# Sheet1.net
KiCad netlist of a schematic drawn in Altium Designer
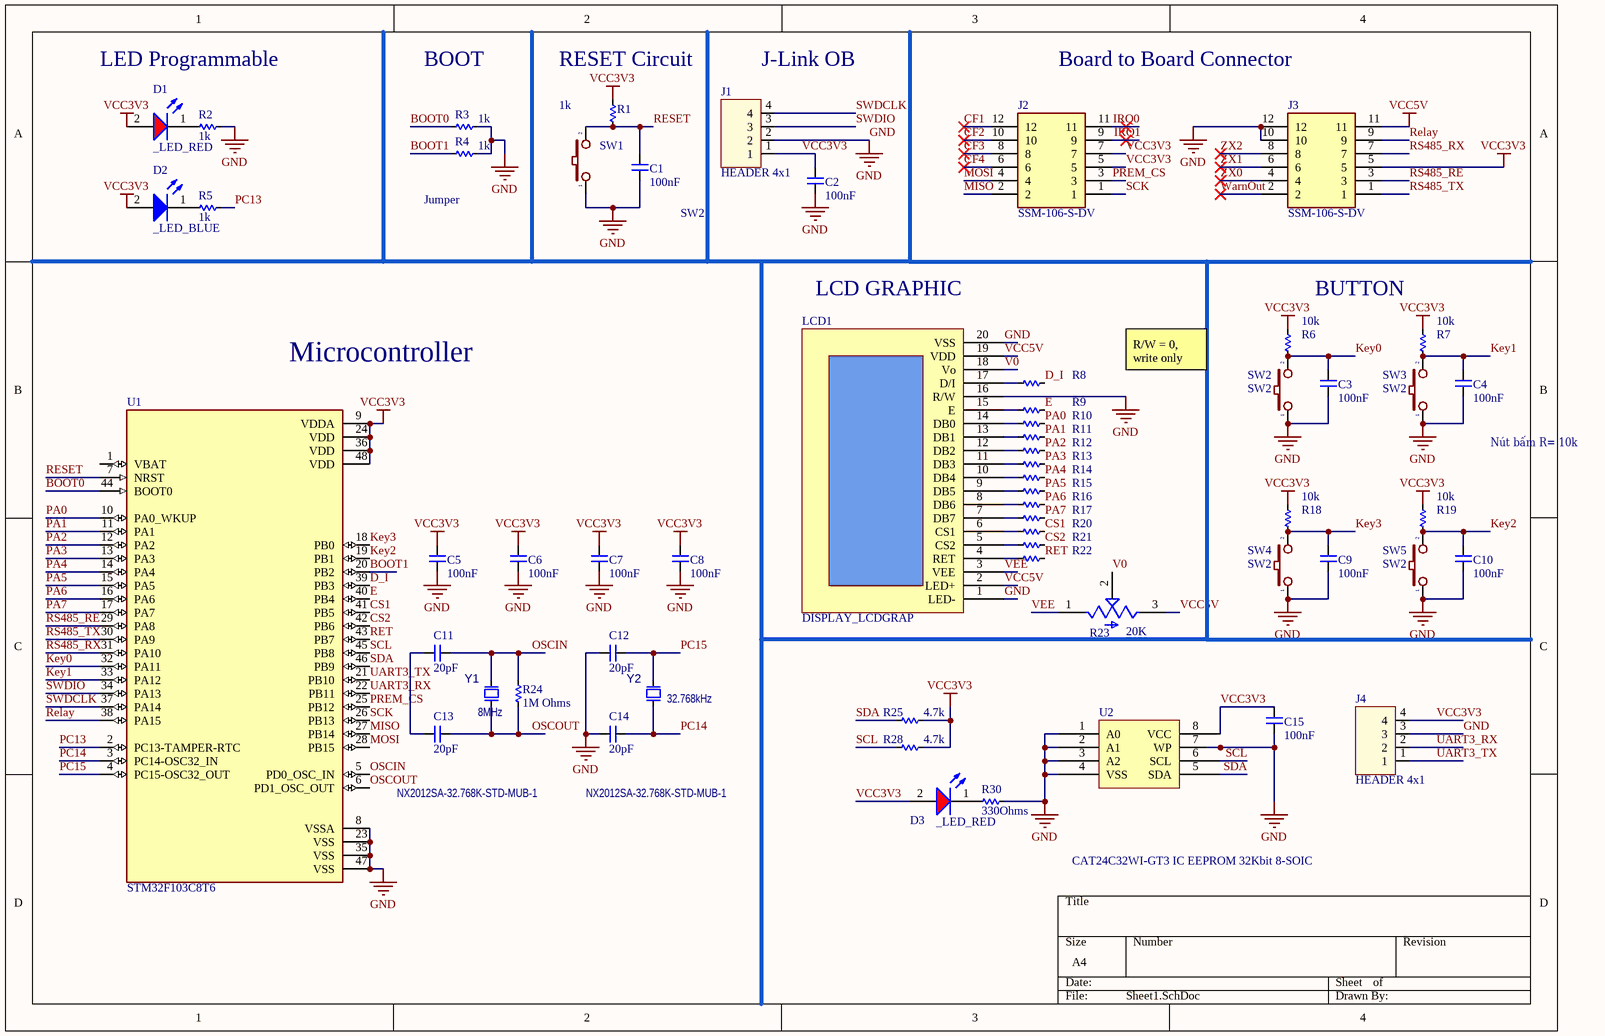
[diagram p0: Sheet1.SchDoc]

(export (version "E")
  (design (tool "Eeschema 10.0.6"))
  (components
    (comp (ref "C1")
      (value "100nF")
      (footprint "CAP_C_2012X110")
      (description "CAP")
      (libsource (lib "Logic_Control_V4") (part "_CAP_C_2"))
    )
    (comp (ref "C2")
      (value "100nF")
      (footprint "CAP_C_2012X110")
      (description "CAP")
      (libsource (lib "Logic_Control_V4") (part "_CAP_C_2"))
    )
    (comp (ref "C3")
      (value "100nF")
      (footprint "CAP_C_2012X110")
      (description "CAP")
      (libsource (lib "Logic_Control_V4") (part "_CAP_C_2"))
    )
    (comp (ref "C4")
      (value "100nF")
      (footprint "CAP_C_2012X110")
      (description "CAP")
      (libsource (lib "Logic_Control_V4") (part "_CAP_C_2"))
    )
    (comp (ref "C5")
      (value "100nF")
      (footprint "CAP_C_2012X110")
      (description "CAP")
      (libsource (lib "Logic_Control_V4") (part "_CAP_C_2"))
    )
    (comp (ref "C6")
      (value "100nF")
      (footprint "CAP_C_2012X110")
      (description "CAP")
      (libsource (lib "Logic_Control_V4") (part "_CAP_C_2"))
    )
    (comp (ref "C7")
      (value "100nF")
      (footprint "CAP_C_2012X110")
      (description "CAP")
      (libsource (lib "Logic_Control_V4") (part "_CAP_C_2"))
    )
    (comp (ref "C8")
      (value "100nF")
      (footprint "CAP_C_2012X110")
      (description "CAP")
      (libsource (lib "Logic_Control_V4") (part "_CAP_C_2"))
    )
    (comp (ref "C9")
      (value "100nF")
      (footprint "CAP_C_2012X110")
      (description "CAP")
      (libsource (lib "Logic_Control_V4") (part "_CAP_C_2"))
    )
    (comp (ref "C10")
      (value "100nF")
      (footprint "CAP_C_2012X110")
      (description "CAP")
      (libsource (lib "Logic_Control_V4") (part "_CAP_C_2"))
    )
    (comp (ref "C11")
      (value "20pF")
      (footprint "CAP_C_2012X110")
      (description "CAP")
      (libsource (lib "Logic_Control_V4") (part "_CAP_C_2"))
    )
    (comp (ref "C12")
      (value "20pF")
      (footprint "CAP_C_2012X110")
      (description "CAP")
      (libsource (lib "Logic_Control_V4") (part "_CAP_C_2"))
    )
    (comp (ref "C13")
      (value "20pF")
      (footprint "CAP_C_2012X110")
      (description "CAP")
      (libsource (lib "Logic_Control_V4") (part "_CAP_C_2"))
    )
    (comp (ref "C14")
      (value "20pF")
      (footprint "CAP_C_2012X110")
      (description "CAP")
      (libsource (lib "Logic_Control_V4") (part "_CAP_C_2"))
    )
    (comp (ref "C15")
      (value "100nF")
      (footprint "CAP_C_2012X110")
      (description "CAP")
      (libsource (lib "Logic_Control_V4") (part "_CAP_C_2"))
    )
    (comp (ref "D1")
      (value "_LED_RED")
      (footprint "LED_0603")
      (libsource (lib "Logic_Control_V4") (part "_LED_RED"))
    )
    (comp (ref "D2")
      (value "_LED_BLUE")
      (footprint "LED_0603")
      (libsource (lib "Logic_Control_V4") (part "_LED_BLUE"))
    )
    (comp (ref "D3")
      (value "_LED_RED")
      (footprint "LED_0603")
      (libsource (lib "Logic_Control_V4") (part "_LED_RED"))
    )
    (comp (ref "J1")
      (value "HEADER 4x1")
      (footprint "Header_254P_4x1")
      (libsource (lib "Logic_Control_V4") (part "Header 4x1"))
    )
    (comp (ref "J2")
      (value "SSM-106-S-DV")
      (footprint "SSM-105-XXX-DV-BE")
      (description "Connector")
      (fields
        (field (name "MANUFACTURER_PART_NUMBER") "SSM-105-S-DV")
        (field (name "MOUSER PART NUMBER") "200-SSM105SDV")
      )
      (libsource (lib "LogicControl_V2") (part "SSM-106-S-DV"))
    )
    (comp (ref "J3")
      (value "SSM-106-S-DV")
      (footprint "SSM-105-XXX-DV-BE")
      (description "Connector")
      (fields
        (field (name "MANUFACTURER_PART_NUMBER") "SSM-105-S-DV")
        (field (name "MOUSER PART NUMBER") "200-SSM105SDV")
      )
      (libsource (lib "LogicControl_V2") (part "SSM-106-S-DV"))
    )
    (comp (ref "J4")
      (value "HEADER 4x1")
      (footprint "Header_254P_4x1")
      (libsource (lib "Logic_Control_V4") (part "Header 4x1"))
    )
    (comp (ref "LCD1")
      (value "DISPLAY_LCDGRAP")
      (footprint "LCD_GRAP_20PIN")
      (description "Display 128x64pixel")
      (fields
        (field (name "MANUFACTURER") "Newhaven Display")
        (field (name "MANUFACTURER PART NUMBER") "NHD-12864AZ-NSW-BBW-TR")
      )
      (libsource (lib "Logic_Control_V4") (part "DISPLAY_LCDGRAP"))
    )
    (comp (ref "R1")
      (value "1k")
      (footprint "RES_C_2012X65")
      (description "RES")
      (libsource (lib "Logic_Control_V4") (part "_RES_B_2"))
    )
    (comp (ref "R2")
      (value "1k")
      (footprint "RES_C_2012X65")
      (description "RES")
      (libsource (lib "Logic_Control_V4") (part "_RES_B_2"))
    )
    (comp (ref "R3")
      (value "1k")
      (footprint "RES_C_2012X65")
      (description "RES")
      (libsource (lib "Logic_Control_V4") (part "_RES_B_2"))
    )
    (comp (ref "R4")
      (value "1k")
      (footprint "RES_C_2012X65")
      (description "RES")
      (libsource (lib "Logic_Control_V4") (part "_RES_B_2"))
    )
    (comp (ref "R5")
      (value "1k")
      (footprint "RES_C_2012X65")
      (description "RES")
      (libsource (lib "Logic_Control_V4") (part "_RES_B_2"))
    )
    (comp (ref "R6")
      (value "10k")
      (footprint "RES_C_2012X65")
      (description "RES")
      (libsource (lib "Logic_Control_V4") (part "_RES_B_2"))
    )
    (comp (ref "R7")
      (value "10k")
      (footprint "RES_C_2012X65")
      (description "RES")
      (libsource (lib "Logic_Control_V4") (part "_RES_B_2"))
    )
    (comp (ref "R8")
      (value "1k")
      (footprint "RES_C_2012X65")
      (description "RES")
      (libsource (lib "Logic_Control_V4") (part "_RES_B_2"))
    )
    (comp (ref "R9")
      (value "1k")
      (footprint "RES_C_2012X65")
      (description "RES")
      (libsource (lib "Logic_Control_V4") (part "_RES_B_2"))
    )
    (comp (ref "R10")
      (value "1k")
      (footprint "RES_C_2012X65")
      (description "RES")
      (libsource (lib "Logic_Control_V4") (part "_RES_B_2"))
    )
    (comp (ref "R11")
      (value "1k")
      (footprint "RES_C_2012X65")
      (description "RES")
      (libsource (lib "Logic_Control_V4") (part "_RES_B_2"))
    )
    (comp (ref "R12")
      (value "1k")
      (footprint "RES_C_2012X65")
      (description "RES")
      (libsource (lib "Logic_Control_V4") (part "_RES_B_2"))
    )
    (comp (ref "R13")
      (value "1k")
      (footprint "RES_C_2012X65")
      (description "RES")
      (libsource (lib "Logic_Control_V4") (part "_RES_B_2"))
    )
    (comp (ref "R14")
      (value "1k")
      (footprint "RES_C_2012X65")
      (description "RES")
      (libsource (lib "Logic_Control_V4") (part "_RES_B_2"))
    )
    (comp (ref "R15")
      (value "1k")
      (footprint "RES_C_2012X65")
      (description "RES")
      (libsource (lib "Logic_Control_V4") (part "_RES_B_2"))
    )
    (comp (ref "R16")
      (value "1k")
      (footprint "RES_C_2012X65")
      (description "RES")
      (libsource (lib "Logic_Control_V4") (part "_RES_B_2"))
    )
    (comp (ref "R17")
      (value "1k")
      (footprint "RES_C_2012X65")
      (description "RES")
      (libsource (lib "Logic_Control_V4") (part "_RES_B_2"))
    )
    (comp (ref "R18")
      (value "10k")
      (footprint "RES_C_2012X65")
      (description "RES")
      (libsource (lib "Logic_Control_V4") (part "_RES_B_2"))
    )
    (comp (ref "R19")
      (value "10k")
      (footprint "RES_C_2012X65")
      (description "RES")
      (libsource (lib "Logic_Control_V4") (part "_RES_B_2"))
    )
    (comp (ref "R20")
      (value "1k")
      (footprint "RES_C_2012X65")
      (description "RES")
      (libsource (lib "Logic_Control_V4") (part "_RES_B_2"))
    )
    (comp (ref "R21")
      (value "1k")
      (footprint "RES_C_2012X65")
      (description "RES")
      (libsource (lib "Logic_Control_V4") (part "_RES_B_2"))
    )
    (comp (ref "R22")
      (value "1k")
      (footprint "RES_C_2012X65")
      (description "RES")
      (libsource (lib "Logic_Control_V4") (part "_RES_B_2"))
    )
    (comp (ref "R23")
      (value "20K")
      (footprint "TRIM_TC33X-2-103E")
      (description "10 kOhms 0.1W, 1/10W J Lead Surface Mount Trimmer Potentiometer Cermet 1 Turn Top Adjustment")
      (fields (field (name "MP") "TC33X-2-103E") (field (name "MF") "Bourns"))
      (libsource (lib "Logic_Control_V4") (part "TC33X-2-103E"))
    )
    (comp (ref "R24")
      (value "1M Ohms")
      (footprint "RES_C_2012X65")
      (description "RES")
      (libsource (lib "Logic_Control_V4") (part "_RES_B_2"))
    )
    (comp (ref "R25")
      (value "4.7k")
      (footprint "RES_C_1608X60")
      (description "RES")
      (libsource (lib "Logic_Control_V4") (part "_RES_B_2_1"))
    )
    (comp (ref "R28")
      (value "4.7k")
      (footprint "RES_C_1608X60")
      (description "RES")
      (libsource (lib "Logic_Control_V4") (part "_RES_B_2_1"))
    )
    (comp (ref "R30")
      (value "330Ohms")
      (footprint "RES_C_1608X60")
      (description "RES")
      (libsource (lib "Logic_Control_V4") (part "_RES_B_2_1"))
    )
    (comp (ref "SW1")
      (value "SW2")
      (footprint "SW2-SMD")
      (description "Switch button 2 pin")
      (libsource (lib "Logic_Control_V4") (part "SW2"))
    )
    (comp (ref "SW2")
      (value "SW2")
      (footprint "SW2-SMD")
      (description "Switch button 2 pin")
      (libsource (lib "Logic_Control_V4") (part "SW2"))
    )
    (comp (ref "SW3")
      (value "SW2")
      (footprint "SW2-SMD")
      (description "Switch button 2 pin")
      (libsource (lib "Logic_Control_V4") (part "SW2"))
    )
    (comp (ref "SW4")
      (value "SW2")
      (footprint "SW2-SMD")
      (description "Switch button 2 pin")
      (libsource (lib "Logic_Control_V4") (part "SW2"))
    )
    (comp (ref "SW5")
      (value "SW2")
      (footprint "SW2-SMD")
      (description "Switch button 2 pin")
      (libsource (lib "Logic_Control_V4") (part "SW2"))
    )
    (comp (ref "U1")
      (value "STM32F103C8T6")
      (footprint "QFP50P900X900X160-48N")
      (description "ARM® Cortex®-M3 STM32F1 Microcontroller IC 32-Bit 72MHz 64KB (64K x 8) FLASH 48-LQFP (7x7)")
      (fields (field (name "MF") "STMicroelectronics"))
      (libsource (lib "Logic_Control_V4") (part "STM32F103C8T6"))
    )
    (comp (ref "U2")
      (value "CAT24C32WI-GT3 IC EEPROM 32Kbit 8-SOIC")
      (footprint "SOP8")
      (libsource (lib "Logic_Control_V4") (part "CAT24C32WI-GT3 IC EEPROM 32Kbit 8-SOIC"))
    )
    (comp (ref "Y1")
      (value "8MHz")
      (footprint "CRYSTAL_NX2012SA")
      (description "Crystal")
      (fields
        (field (name "TOLERANCE") "±20ppm")
        (field (name "MANUFACTURER PART NUMBER 1") "NX2012SA-32.768K-STD-MUB-1")
        (field (name "Comment") "Crystal 2 Pins")
        (field (name "OWNER") "Jamus Griego")
      )
      (libsource (lib "Logic_Control_V4") (part "OSC_32.768kHz"))
    )
    (comp (ref "Y2")
      (value "32.768kHz")
      (footprint "CRYSTAL_NX2012SA")
      (description "Crystal")
      (fields
        (field (name "TOLERANCE") "±20ppm")
        (field (name "MANUFACTURER PART NUMBER 1") "NX2012SA-32.768K-STD-MUB-1")
        (field (name "Comment") "Crystal 2 Pins")
        (field (name "OWNER") "Jamus Griego")
      )
      (libsource (lib "Logic_Control_V4") (part "OSC_32.768kHz"))
    )
  )
  (nets
    (net (code "1") (name "/BOOT0") (class "Default")
      (node (ref "R3") (pin "1") (pinfunction "1_1") (pintype "passive"))
      (node (ref "U1") (pin "44") (pinfunction "BOOT0_44") (pintype "input"))
    )
    (net (code "2") (name "/BOOT1") (class "Default")
      (node (ref "R4") (pin "1") (pinfunction "1_1") (pintype "passive"))
      (node (ref "U1") (pin "20") (pinfunction "PB2_20") (pintype "bidirectional"))
    )
    (net (code "3") (name "/CF1") (class "Default")
      (node (ref "J2") (pin "12") (pinfunction "12_12") (pintype "passive+no_connect"))
    )
    (net (code "4") (name "/CF2") (class "Default")
      (node (ref "J2") (pin "10") (pinfunction "10_10") (pintype "passive+no_connect"))
    )
    (net (code "5") (name "/CF3") (class "Default")
      (node (ref "J2") (pin "8") (pinfunction "8_8") (pintype "passive+no_connect"))
    )
    (net (code "6") (name "/CF4") (class "Default")
      (node (ref "J2") (pin "6") (pinfunction "6_6") (pintype "passive+no_connect"))
    )
    (net (code "7") (name "/CS1") (class "Default")
      (node (ref "R20") (pin "2") (pinfunction "2_2") (pintype "passive"))
      (node (ref "U1") (pin "41") (pinfunction "PB5_41") (pintype "bidirectional"))
    )
    (net (code "8") (name "/CS2") (class "Default")
      (node (ref "R21") (pin "2") (pinfunction "2_2") (pintype "passive"))
      (node (ref "U1") (pin "42") (pinfunction "PB6_42") (pintype "bidirectional"))
    )
    (net (code "9") (name "/D_I") (class "Default")
      (node (ref "R8") (pin "2") (pinfunction "2_2") (pintype "passive"))
      (node (ref "U1") (pin "39") (pinfunction "PB3_39") (pintype "bidirectional"))
    )
    (net (code "10") (name "/E") (class "Default")
      (node (ref "R9") (pin "2") (pinfunction "2_2") (pintype "passive"))
      (node (ref "U1") (pin "40") (pinfunction "PB4_40") (pintype "bidirectional"))
    )
    (net (code "11") (name "/IRQ0") (class "Default")
      (node (ref "J2") (pin "11") (pinfunction "11_11") (pintype "passive"))
    )
    (net (code "12") (name "/IRQ1") (class "Default")
      (node (ref "J2") (pin "9") (pinfunction "9_9") (pintype "passive"))
    )
    (net (code "13") (name "/Key0") (class "Default")
      (node (ref "C3") (pin "2") (pinfunction "2_2") (pintype "passive"))
      (node (ref "R6") (pin "1") (pinfunction "1_1") (pintype "passive"))
      (node (ref "SW2") (pin "2") (pinfunction "2_2") (pintype "passive"))
      (node (ref "U1") (pin "32") (pinfunction "PA11_32") (pintype "bidirectional"))
    )
    (net (code "14") (name "/Key1") (class "Default")
      (node (ref "C4") (pin "2") (pinfunction "2_2") (pintype "passive"))
      (node (ref "R7") (pin "1") (pinfunction "1_1") (pintype "passive"))
      (node (ref "SW3") (pin "2") (pinfunction "2_2") (pintype "passive"))
      (node (ref "U1") (pin "33") (pinfunction "PA12_33") (pintype "bidirectional"))
    )
    (net (code "15") (name "/Key2") (class "Default")
      (node (ref "C10") (pin "2") (pinfunction "2_2") (pintype "passive"))
      (node (ref "R19") (pin "1") (pinfunction "1_1") (pintype "passive"))
      (node (ref "SW5") (pin "2") (pinfunction "2_2") (pintype "passive"))
      (node (ref "U1") (pin "19") (pinfunction "PB1_19") (pintype "bidirectional"))
    )
    (net (code "16") (name "/Key3") (class "Default")
      (node (ref "C9") (pin "2") (pinfunction "2_2") (pintype "passive"))
      (node (ref "R18") (pin "1") (pinfunction "1_1") (pintype "passive"))
      (node (ref "SW4") (pin "2") (pinfunction "2_2") (pintype "passive"))
      (node (ref "U1") (pin "18") (pinfunction "PB0_18") (pintype "bidirectional"))
    )
    (net (code "17") (name "/MISO") (class "Default")
      (node (ref "J2") (pin "2") (pinfunction "2_2") (pintype "passive"))
      (node (ref "U1") (pin "27") (pinfunction "PB14_27") (pintype "bidirectional"))
    )
    (net (code "18") (name "/MOSI") (class "Default")
      (node (ref "J2") (pin "4") (pinfunction "4_4") (pintype "passive"))
      (node (ref "U1") (pin "28") (pinfunction "PB15_28") (pintype "bidirectional"))
    )
    (net (code "19") (name "/OSCIN") (class "Default")
      (node (ref "C11") (pin "2") (pinfunction "2_2") (pintype "passive"))
      (node (ref "R24") (pin "2") (pinfunction "2_2") (pintype "passive"))
      (node (ref "U1") (pin "5") (pinfunction "PD0_OSC_IN_5") (pintype "bidirectional"))
      (node (ref "Y1") (pin "2") (pinfunction "Osc2_2") (pintype "passive"))
    )
    (net (code "20") (name "/OSCOUT") (class "Default")
      (node (ref "C13") (pin "2") (pinfunction "2_2") (pintype "passive"))
      (node (ref "R24") (pin "1") (pinfunction "1_1") (pintype "passive"))
      (node (ref "U1") (pin "6") (pinfunction "PD1_OSC_OUT_6") (pintype "bidirectional"))
      (node (ref "Y1") (pin "1") (pinfunction "Osc1_1") (pintype "passive"))
    )
    (net (code "21") (name "/PA0") (class "Default")
      (node (ref "R10") (pin "2") (pinfunction "2_2") (pintype "passive"))
      (node (ref "U1") (pin "10") (pinfunction "PA0_WKUP_10") (pintype "bidirectional"))
    )
    (net (code "22") (name "/PA1") (class "Default")
      (node (ref "R11") (pin "2") (pinfunction "2_2") (pintype "passive"))
      (node (ref "U1") (pin "11") (pinfunction "PA1_11") (pintype "bidirectional"))
    )
    (net (code "23") (name "/PA2") (class "Default")
      (node (ref "R12") (pin "2") (pinfunction "2_2") (pintype "passive"))
      (node (ref "U1") (pin "12") (pinfunction "PA2_12") (pintype "bidirectional"))
    )
    (net (code "24") (name "/PA3") (class "Default")
      (node (ref "R13") (pin "2") (pinfunction "2_2") (pintype "passive"))
      (node (ref "U1") (pin "13") (pinfunction "PA3_13") (pintype "bidirectional"))
    )
    (net (code "25") (name "/PA4") (class "Default")
      (node (ref "R14") (pin "2") (pinfunction "2_2") (pintype "passive"))
      (node (ref "U1") (pin "14") (pinfunction "PA4_14") (pintype "bidirectional"))
    )
    (net (code "26") (name "/PA5") (class "Default")
      (node (ref "R15") (pin "2") (pinfunction "2_2") (pintype "passive"))
      (node (ref "U1") (pin "15") (pinfunction "PA5_15") (pintype "bidirectional"))
    )
    (net (code "27") (name "/PA6") (class "Default")
      (node (ref "R16") (pin "2") (pinfunction "2_2") (pintype "passive"))
      (node (ref "U1") (pin "16") (pinfunction "PA6_16") (pintype "bidirectional"))
    )
    (net (code "28") (name "/PA7") (class "Default")
      (node (ref "R17") (pin "2") (pinfunction "2_2") (pintype "passive"))
      (node (ref "U1") (pin "17") (pinfunction "PA7_17") (pintype "bidirectional"))
    )
    (net (code "29") (name "/PC13") (class "Default")
      (node (ref "R5") (pin "2") (pinfunction "2_2") (pintype "passive"))
      (node (ref "U1") (pin "2") (pinfunction "PC13-TAMPER-RTC_2") (pintype "bidirectional"))
    )
    (net (code "30") (name "/PC14") (class "Default")
      (node (ref "C14") (pin "2") (pinfunction "2_2") (pintype "passive"))
      (node (ref "U1") (pin "3") (pinfunction "PC14-OSC32_IN_3") (pintype "bidirectional"))
      (node (ref "Y2") (pin "1") (pinfunction "Osc1_1") (pintype "passive"))
    )
    (net (code "31") (name "/PC15") (class "Default")
      (node (ref "C12") (pin "2") (pinfunction "2_2") (pintype "passive"))
      (node (ref "U1") (pin "4") (pinfunction "PC15-OSC32_OUT_4") (pintype "bidirectional"))
      (node (ref "Y2") (pin "2") (pinfunction "Osc2_2") (pintype "passive"))
    )
    (net (code "32") (name "/PREM_CS") (class "Default")
      (node (ref "J2") (pin "3") (pinfunction "3_3") (pintype "passive"))
      (node (ref "U1") (pin "25") (pinfunction "PB12_25") (pintype "bidirectional"))
    )
    (net (code "33") (name "/RESET") (class "Default")
      (node (ref "C1") (pin "2") (pinfunction "2_2") (pintype "passive"))
      (node (ref "R1") (pin "1") (pinfunction "1_1") (pintype "passive"))
      (node (ref "SW1") (pin "2") (pinfunction "2_2") (pintype "passive"))
      (node (ref "U1") (pin "7") (pinfunction "NRST_7") (pintype "input"))
    )
    (net (code "34") (name "/RET") (class "Default")
      (node (ref "R22") (pin "2") (pinfunction "2_2") (pintype "passive"))
      (node (ref "U1") (pin "43") (pinfunction "PB7_43") (pintype "bidirectional"))
    )
    (net (code "35") (name "/RS485_RE") (class "Default")
      (node (ref "J3") (pin "3") (pinfunction "3_3") (pintype "passive"))
      (node (ref "U1") (pin "29") (pinfunction "PA8_29") (pintype "bidirectional"))
    )
    (net (code "36") (name "/RS485_RX") (class "Default")
      (node (ref "J3") (pin "7") (pinfunction "7_7") (pintype "passive"))
      (node (ref "U1") (pin "31") (pinfunction "PA10_31") (pintype "bidirectional"))
    )
    (net (code "37") (name "/RS485_TX") (class "Default")
      (node (ref "J3") (pin "1") (pinfunction "1_1") (pintype "passive"))
      (node (ref "U1") (pin "30") (pinfunction "PA9_30") (pintype "bidirectional"))
    )
    (net (code "38") (name "/Relay") (class "Default")
      (node (ref "J3") (pin "9") (pinfunction "9_9") (pintype "passive"))
      (node (ref "U1") (pin "38") (pinfunction "PA15_38") (pintype "bidirectional"))
    )
    (net (code "39") (name "/SCK") (class "Default")
      (node (ref "J2") (pin "1") (pinfunction "1_1") (pintype "passive"))
      (node (ref "U1") (pin "26") (pinfunction "PB13_26") (pintype "bidirectional"))
    )
    (net (code "40") (name "/SCL") (class "Default")
      (node (ref "R28") (pin "1") (pinfunction "1_1") (pintype "passive"))
      (node (ref "U1") (pin "45") (pinfunction "PB8_45") (pintype "bidirectional"))
      (node (ref "U2") (pin "6") (pinfunction "SCL_6") (pintype "passive"))
    )
    (net (code "41") (name "/SDA") (class "Default")
      (node (ref "R25") (pin "1") (pinfunction "1_1") (pintype "passive"))
      (node (ref "U1") (pin "46") (pinfunction "PB9_46") (pintype "bidirectional"))
      (node (ref "U2") (pin "5") (pinfunction "SDA_5") (pintype "passive"))
    )
    (net (code "42") (name "/SWDCLK") (class "Default")
      (node (ref "J1") (pin "4") (pinfunction "4_4") (pintype "passive"))
      (node (ref "U1") (pin "37") (pinfunction "PA14_37") (pintype "bidirectional"))
    )
    (net (code "43") (name "/SWDIO") (class "Default")
      (node (ref "J1") (pin "3") (pinfunction "3_3") (pintype "passive"))
      (node (ref "U1") (pin "34") (pinfunction "PA13_34") (pintype "bidirectional"))
    )
    (net (code "44") (name "/UART3_RX") (class "Default")
      (node (ref "J4") (pin "2") (pinfunction "2_2") (pintype "passive"))
      (node (ref "U1") (pin "22") (pinfunction "PB11_22") (pintype "bidirectional"))
    )
    (net (code "45") (name "/UART3_TX") (class "Default")
      (node (ref "J4") (pin "1") (pinfunction "1_1") (pintype "passive"))
      (node (ref "U1") (pin "21") (pinfunction "PB10_21") (pintype "bidirectional"))
    )
    (net (code "46") (name "/V0") (class "Default")
      (node (ref "LCD1") (pin "18") (pinfunction "Vo_18") (pintype "power_in"))
      (node (ref "R23") (pin "2") (pinfunction "W_2") (pintype "passive"))
    )
    (net (code "47") (name "/VEE") (class "Default")
      (node (ref "LCD1") (pin "3") (pinfunction "VEE_3") (pintype "power_in"))
      (node (ref "R23") (pin "1") (pinfunction "CCW_1") (pintype "passive"))
    )
    (net (code "48") (name "/WarnOut") (class "Default")
      (node (ref "J3") (pin "2") (pinfunction "2_2") (pintype "passive+no_connect"))
    )
    (net (code "49") (name "/ZX0") (class "Default")
      (node (ref "J3") (pin "4") (pinfunction "4_4") (pintype "passive+no_connect"))
    )
    (net (code "50") (name "/ZX1") (class "Default")
      (node (ref "J3") (pin "6") (pinfunction "6_6") (pintype "passive+no_connect"))
    )
    (net (code "51") (name "/ZX2") (class "Default")
      (node (ref "J3") (pin "8") (pinfunction "8_8") (pintype "passive+no_connect"))
    )
    (net (code "52") (name "GND") (class "Default")
      (node (ref "C1") (pin "1") (pinfunction "1_1") (pintype "passive"))
      (node (ref "C10") (pin "1") (pinfunction "1_1") (pintype "passive"))
      (node (ref "C12") (pin "1") (pinfunction "1_1") (pintype "passive"))
      (node (ref "C14") (pin "1") (pinfunction "1_1") (pintype "passive"))
      (node (ref "C15") (pin "1") (pinfunction "1_1") (pintype "passive"))
      (node (ref "C2") (pin "1") (pinfunction "1_1") (pintype "passive"))
      (node (ref "C3") (pin "1") (pinfunction "1_1") (pintype "passive"))
      (node (ref "C4") (pin "1") (pinfunction "1_1") (pintype "passive"))
      (node (ref "C5") (pin "1") (pinfunction "1_1") (pintype "passive"))
      (node (ref "C6") (pin "1") (pinfunction "1_1") (pintype "passive"))
      (node (ref "C7") (pin "1") (pinfunction "1_1") (pintype "passive"))
      (node (ref "C8") (pin "1") (pinfunction "1_1") (pintype "passive"))
      (node (ref "C9") (pin "1") (pinfunction "1_1") (pintype "passive"))
      (node (ref "J1") (pin "2") (pinfunction "2_2") (pintype "passive"))
      (node (ref "J3") (pin "10") (pinfunction "10_10") (pintype "passive"))
      (node (ref "J3") (pin "12") (pinfunction "12_12") (pintype "passive"))
      (node (ref "J4") (pin "3") (pinfunction "3_3") (pintype "passive"))
      (node (ref "LCD1") (pin "1") (pinfunction "LED-_1") (pintype "power_in"))
      (node (ref "LCD1") (pin "16") (pinfunction "R/W_16") (pintype "passive"))
      (node (ref "LCD1") (pin "20") (pinfunction "VSS_20") (pintype "power_in"))
      (node (ref "R2") (pin "2") (pinfunction "2_2") (pintype "passive"))
      (node (ref "R3") (pin "2") (pinfunction "2_2") (pintype "passive"))
      (node (ref "R30") (pin "2") (pinfunction "2_2") (pintype "passive"))
      (node (ref "R4") (pin "2") (pinfunction "2_2") (pintype "passive"))
      (node (ref "SW1") (pin "1") (pinfunction "1_1") (pintype "passive"))
      (node (ref "SW2") (pin "1") (pinfunction "1_1") (pintype "passive"))
      (node (ref "SW3") (pin "1") (pinfunction "1_1") (pintype "passive"))
      (node (ref "SW4") (pin "1") (pinfunction "1_1") (pintype "passive"))
      (node (ref "SW5") (pin "1") (pinfunction "1_1") (pintype "passive"))
      (node (ref "U1") (pin "23") (pinfunction "VSS_23") (pintype "power_in"))
      (node (ref "U1") (pin "35") (pinfunction "VSS_35") (pintype "power_in"))
      (node (ref "U1") (pin "47") (pinfunction "VSS_47") (pintype "power_in"))
      (node (ref "U1") (pin "8") (pinfunction "VSSA_8") (pintype "power_in"))
      (node (ref "U2") (pin "1") (pinfunction "A0_1") (pintype "passive"))
      (node (ref "U2") (pin "2") (pinfunction "A1_2") (pintype "passive"))
      (node (ref "U2") (pin "3") (pinfunction "A2_3") (pintype "passive"))
      (node (ref "U2") (pin "4") (pinfunction "VSS_4") (pintype "passive"))
      (node (ref "U2") (pin "7") (pinfunction "WP_7") (pintype "passive"))
    )
    (net (code "53") (name "Net-(C11-Pad1)") (class "Default")
      (node (ref "C11") (pin "1") (pinfunction "1_1") (pintype "passive"))
      (node (ref "C13") (pin "1") (pinfunction "1_1") (pintype "passive"))
    )
    (net (code "54") (name "Net-(D1-K)") (class "Default")
      (node (ref "D1") (pin "1") (pinfunction "K_1") (pintype "passive"))
      (node (ref "R2") (pin "1") (pinfunction "1_1") (pintype "passive"))
    )
    (net (code "55") (name "Net-(D2-K)") (class "Default")
      (node (ref "D2") (pin "1") (pinfunction "K_1") (pintype "passive"))
      (node (ref "R5") (pin "1") (pinfunction "1_1") (pintype "passive"))
    )
    (net (code "56") (name "Net-(D3-K)") (class "Default")
      (node (ref "D3") (pin "1") (pinfunction "K_1") (pintype "passive"))
      (node (ref "R30") (pin "1") (pinfunction "1_1") (pintype "passive"))
    )
    (net (code "57") (name "Net-(LCD1-CS1)") (class "Default")
      (node (ref "LCD1") (pin "6") (pinfunction "CS1_6") (pintype "passive"))
      (node (ref "R20") (pin "1") (pinfunction "1_1") (pintype "passive"))
    )
    (net (code "58") (name "Net-(LCD1-CS2)") (class "Default")
      (node (ref "LCD1") (pin "5") (pinfunction "CS2_5") (pintype "passive"))
      (node (ref "R21") (pin "1") (pinfunction "1_1") (pintype "passive"))
    )
    (net (code "59") (name "Net-(LCD1-DB0)") (class "Default")
      (node (ref "LCD1") (pin "14") (pinfunction "DB0_14") (pintype "passive"))
      (node (ref "R10") (pin "1") (pinfunction "1_1") (pintype "passive"))
    )
    (net (code "60") (name "Net-(LCD1-DB1)") (class "Default")
      (node (ref "LCD1") (pin "13") (pinfunction "DB1_13") (pintype "passive"))
      (node (ref "R11") (pin "1") (pinfunction "1_1") (pintype "passive"))
    )
    (net (code "61") (name "Net-(LCD1-DB2)") (class "Default")
      (node (ref "LCD1") (pin "12") (pinfunction "DB2_12") (pintype "passive"))
      (node (ref "R12") (pin "1") (pinfunction "1_1") (pintype "passive"))
    )
    (net (code "62") (name "Net-(LCD1-DB3)") (class "Default")
      (node (ref "LCD1") (pin "11") (pinfunction "DB3_11") (pintype "passive"))
      (node (ref "R13") (pin "1") (pinfunction "1_1") (pintype "passive"))
    )
    (net (code "63") (name "Net-(LCD1-DB4)") (class "Default")
      (node (ref "LCD1") (pin "10") (pinfunction "DB4_10") (pintype "passive"))
      (node (ref "R14") (pin "1") (pinfunction "1_1") (pintype "passive"))
    )
    (net (code "64") (name "Net-(LCD1-DB5)") (class "Default")
      (node (ref "LCD1") (pin "9") (pinfunction "DB5_9") (pintype "passive"))
      (node (ref "R15") (pin "1") (pinfunction "1_1") (pintype "passive"))
    )
    (net (code "65") (name "Net-(LCD1-DB6)") (class "Default")
      (node (ref "LCD1") (pin "8") (pinfunction "DB6_8") (pintype "passive"))
      (node (ref "R16") (pin "1") (pinfunction "1_1") (pintype "passive"))
    )
    (net (code "66") (name "Net-(LCD1-DB7)") (class "Default")
      (node (ref "LCD1") (pin "7") (pinfunction "DB7_7") (pintype "passive"))
      (node (ref "R17") (pin "1") (pinfunction "1_1") (pintype "passive"))
    )
    (net (code "67") (name "Net-(LCD1-D{slash}I)") (class "Default")
      (node (ref "LCD1") (pin "17") (pinfunction "D/I_17") (pintype "passive"))
      (node (ref "R8") (pin "1") (pinfunction "1_1") (pintype "passive"))
    )
    (net (code "68") (name "Net-(LCD1-E)") (class "Default")
      (node (ref "LCD1") (pin "15") (pinfunction "E_15") (pintype "passive"))
      (node (ref "R9") (pin "1") (pinfunction "1_1") (pintype "passive"))
    )
    (net (code "69") (name "Net-(LCD1-RET)") (class "Default")
      (node (ref "LCD1") (pin "4") (pinfunction "RET_4") (pintype "passive"))
      (node (ref "R22") (pin "1") (pinfunction "1_1") (pintype "passive"))
    )
    (net (code "70") (name "VCC3V3") (class "Default")
      (node (ref "C15") (pin "2") (pinfunction "2_2") (pintype "passive"))
      (node (ref "C2") (pin "2") (pinfunction "2_2") (pintype "passive"))
      (node (ref "C5") (pin "2") (pinfunction "2_2") (pintype "passive"))
      (node (ref "C6") (pin "2") (pinfunction "2_2") (pintype "passive"))
      (node (ref "C7") (pin "2") (pinfunction "2_2") (pintype "passive"))
      (node (ref "C8") (pin "2") (pinfunction "2_2") (pintype "passive"))
      (node (ref "D1") (pin "2") (pinfunction "A_2") (pintype "passive"))
      (node (ref "D2") (pin "2") (pinfunction "A_2") (pintype "passive"))
      (node (ref "D3") (pin "2") (pinfunction "A_2") (pintype "passive"))
      (node (ref "J1") (pin "1") (pinfunction "1_1") (pintype "passive"))
      (node (ref "J2") (pin "5") (pinfunction "5_5") (pintype "passive"))
      (node (ref "J2") (pin "7") (pinfunction "7_7") (pintype "passive"))
      (node (ref "J3") (pin "5") (pinfunction "5_5") (pintype "passive"))
      (node (ref "J4") (pin "4") (pinfunction "4_4") (pintype "passive"))
      (node (ref "R1") (pin "2") (pinfunction "2_2") (pintype "passive"))
      (node (ref "R18") (pin "2") (pinfunction "2_2") (pintype "passive"))
      (node (ref "R19") (pin "2") (pinfunction "2_2") (pintype "passive"))
      (node (ref "R25") (pin "2") (pinfunction "2_2") (pintype "passive"))
      (node (ref "R28") (pin "2") (pinfunction "2_2") (pintype "passive"))
      (node (ref "R6") (pin "2") (pinfunction "2_2") (pintype "passive"))
      (node (ref "R7") (pin "2") (pinfunction "2_2") (pintype "passive"))
      (node (ref "U1") (pin "24") (pinfunction "VDD_24") (pintype "power_in"))
      (node (ref "U1") (pin "36") (pinfunction "VDD_36") (pintype "power_in"))
      (node (ref "U1") (pin "48") (pinfunction "VDD_48") (pintype "power_in"))
      (node (ref "U1") (pin "9") (pinfunction "VDDA_9") (pintype "power_in"))
      (node (ref "U2") (pin "8") (pinfunction "VCC_8") (pintype "passive"))
    )
    (net (code "71") (name "VCC5V") (class "Default")
      (node (ref "J3") (pin "11") (pinfunction "11_11") (pintype "passive"))
      (node (ref "LCD1") (pin "19") (pinfunction "VDD_19") (pintype "power_in"))
      (node (ref "LCD1") (pin "2") (pinfunction "LED+_2") (pintype "power_in"))
      (node (ref "R23") (pin "3") (pinfunction "CW_3") (pintype "passive"))
    )
    (net (code "72") (name "unconnected-(U1-VBAT-Pad1)") (class "Default")
      (node (ref "U1") (pin "1") (pinfunction "VBAT_1") (pintype "bidirectional"))
    )
  )
)
